# RPi_Pico_2.net
KiCad netlist of a schematic drawn in EasyEDA Pro
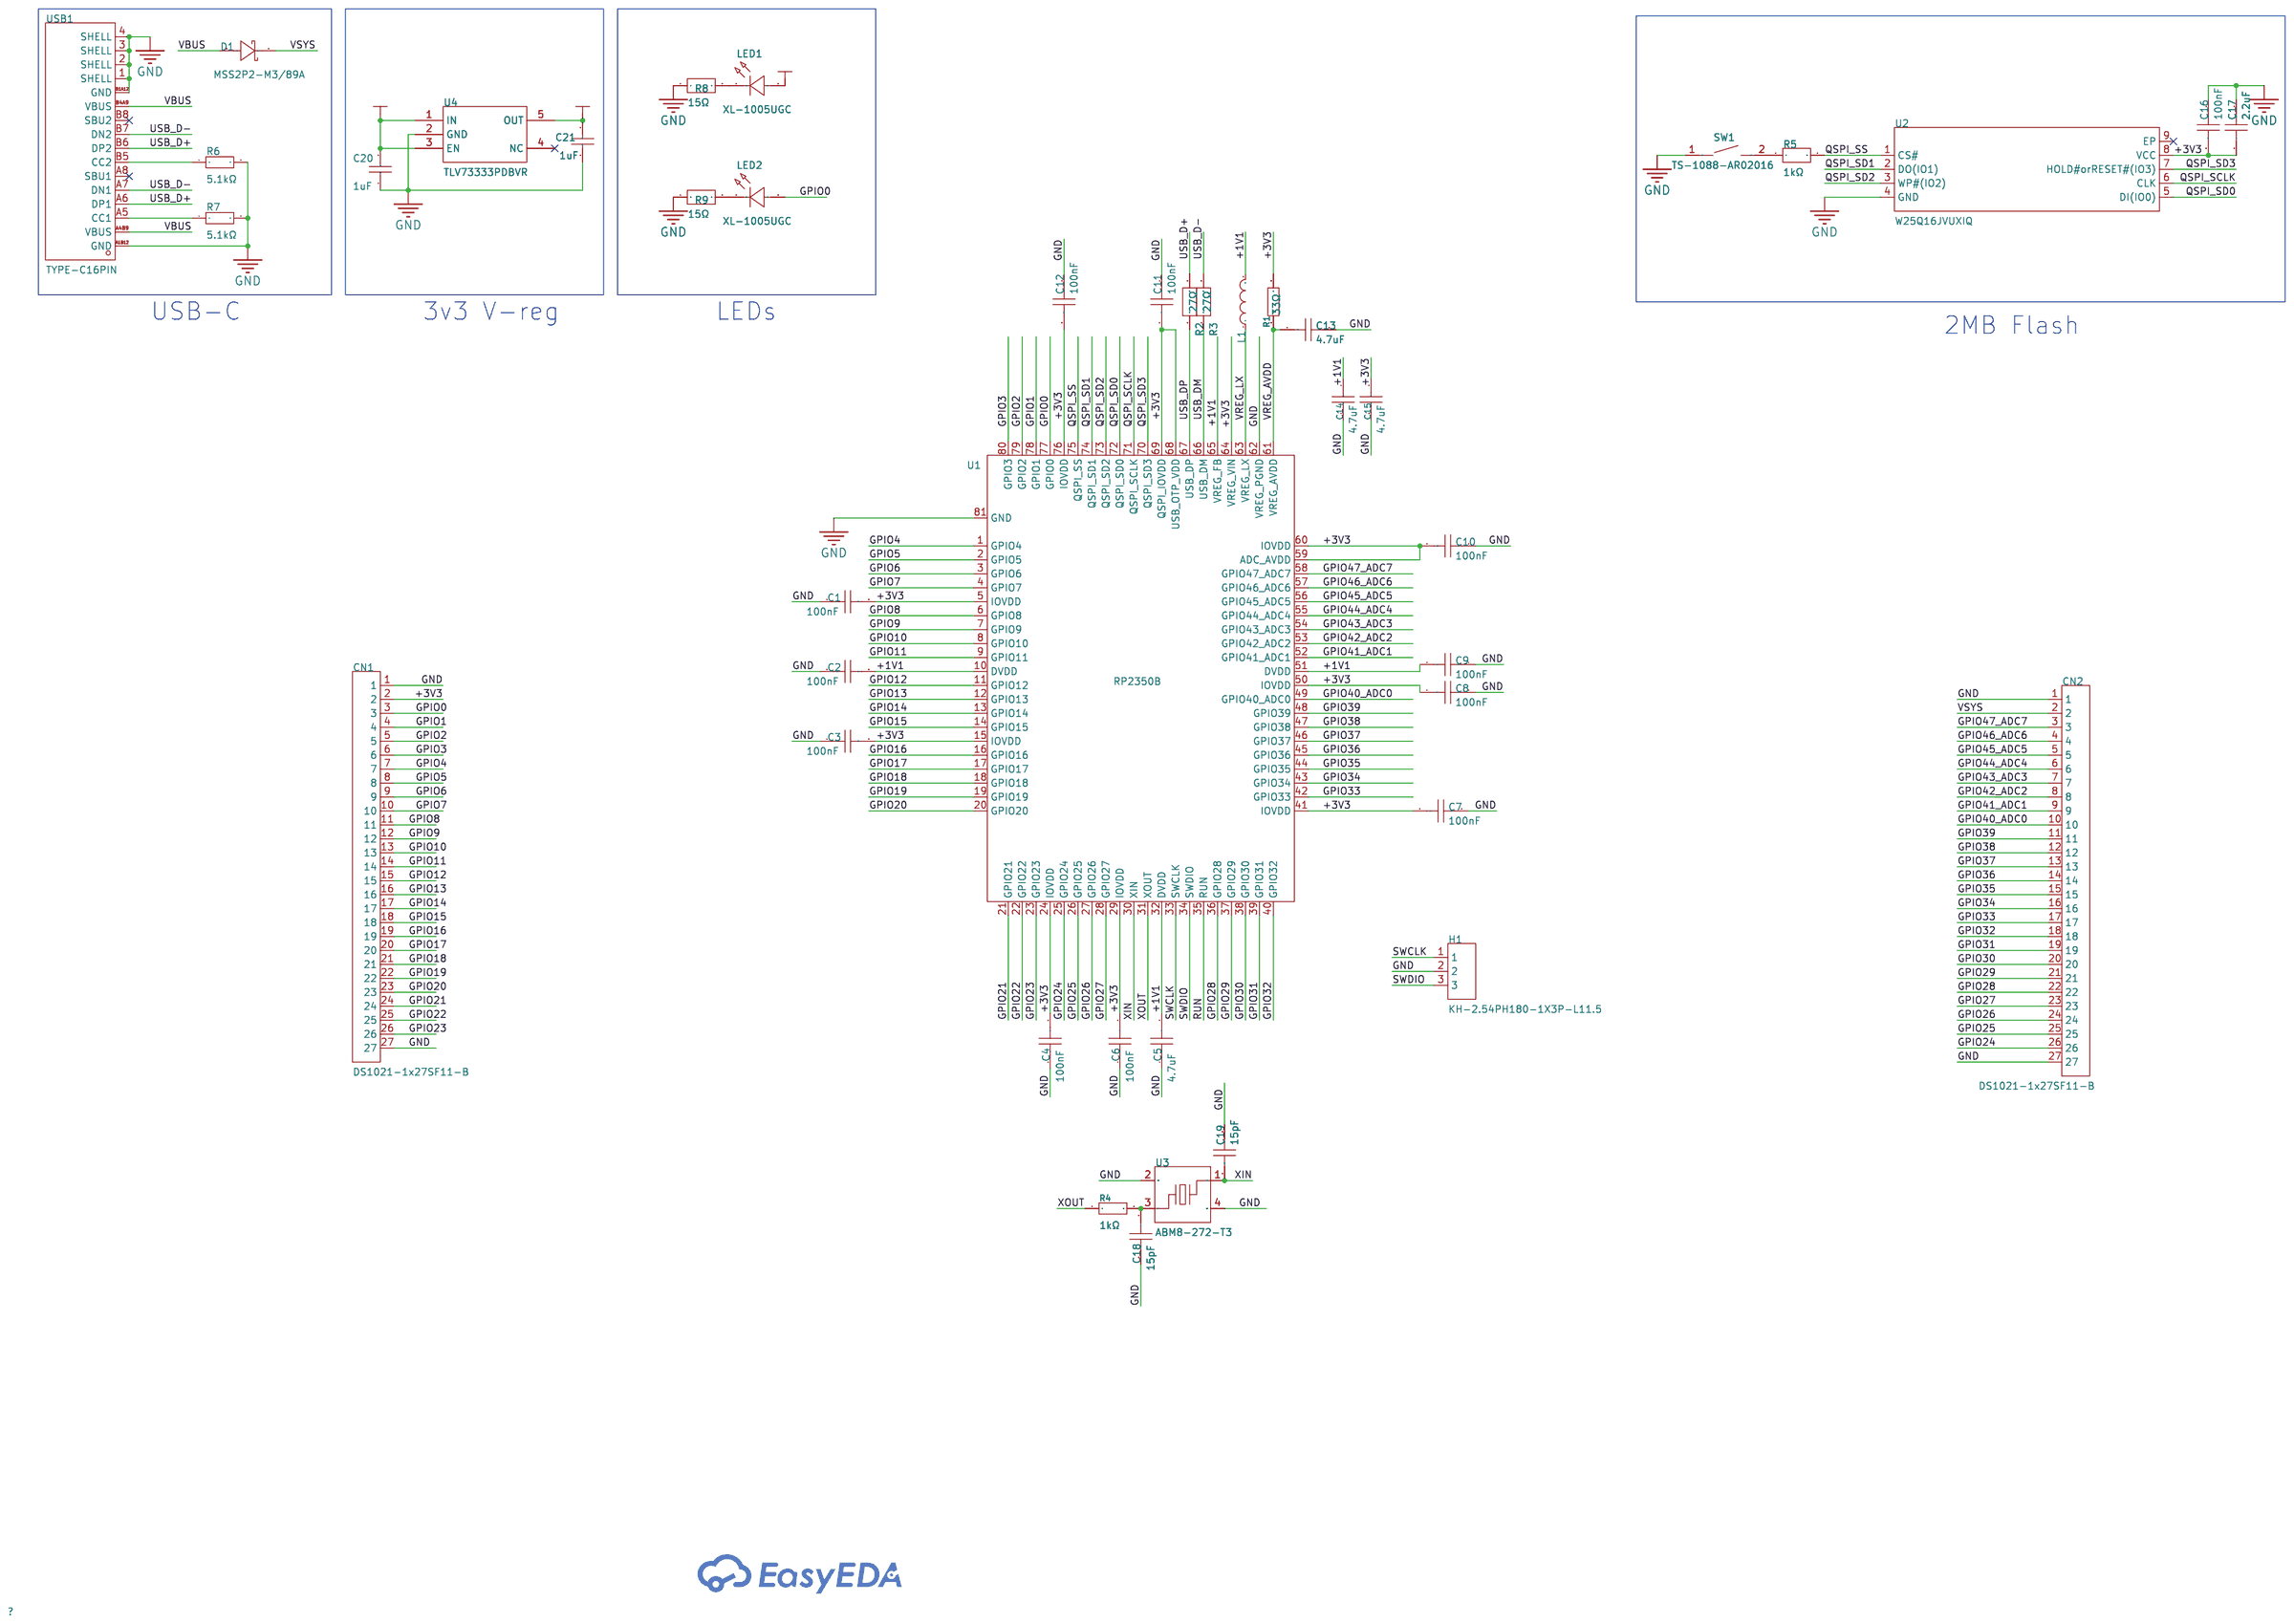
[diagram p0: schematic sheet]

(export (version "E")
  (design (tool "Eeschema 10.0.6"))
  (components
    (comp (ref "C1")
      (value "100nF")
      (footprint "easyedapro:C0201")
      (fields
        (field (name "Manufacturer Part") "GRM033R60J104KE19D")
        (field (name "Manufacturer") "muRata(村田)")
      )
      (libsource (lib "easyedapro") (part "GRM033R60J104KE19D"))
    )
    (comp (ref "C2")
      (value "100nF")
      (footprint "easyedapro:C0201")
      (fields
        (field (name "Manufacturer Part") "GRM033R60J104KE19D")
        (field (name "Manufacturer") "muRata(村田)")
      )
      (libsource (lib "easyedapro") (part "GRM033R60J104KE19D"))
    )
    (comp (ref "C3")
      (value "100nF")
      (footprint "easyedapro:C0201")
      (fields
        (field (name "Manufacturer Part") "GRM033R60J104KE19D")
        (field (name "Manufacturer") "muRata(村田)")
      )
      (libsource (lib "easyedapro") (part "GRM033R60J104KE19D"))
    )
    (comp (ref "C4")
      (value "100nF")
      (footprint "easyedapro:C0201")
      (fields
        (field (name "Manufacturer Part") "GRM033R60J104KE19D")
        (field (name "Manufacturer") "muRata(村田)")
      )
      (libsource (lib "easyedapro") (part "GRM033R60J104KE19D"))
    )
    (comp (ref "C5")
      (value "4.7uF")
      (footprint "easyedapro:C0201")
      (description "Capacitance:4.7uF Tolerance:±20% Tolerance:±20% Voltage Rating:6.3V Temperature Coefficient:X5R")
      (fields
        (field (name "Manufacturer Part") "GRM035R60J475ME15D")
        (field (name "Manufacturer") "muRata(村田)")
      )
      (libsource (lib "easyedapro") (part "GRM035R60J475ME15D"))
    )
    (comp (ref "C6")
      (value "100nF")
      (footprint "easyedapro:C0201")
      (fields
        (field (name "Manufacturer Part") "GRM033R60J104KE19D")
        (field (name "Manufacturer") "muRata(村田)")
      )
      (libsource (lib "easyedapro") (part "GRM033R60J104KE19D"))
    )
    (comp (ref "C7")
      (value "100nF")
      (footprint "easyedapro:C0201")
      (fields
        (field (name "Manufacturer Part") "GRM033R60J104KE19D")
        (field (name "Manufacturer") "muRata(村田)")
      )
      (libsource (lib "easyedapro") (part "GRM033R60J104KE19D"))
    )
    (comp (ref "C8")
      (value "100nF")
      (footprint "easyedapro:C0201")
      (fields
        (field (name "Manufacturer Part") "GRM033R60J104KE19D")
        (field (name "Manufacturer") "muRata(村田)")
      )
      (libsource (lib "easyedapro") (part "GRM033R60J104KE19D"))
    )
    (comp (ref "C9")
      (value "100nF")
      (footprint "easyedapro:C0201")
      (fields
        (field (name "Manufacturer Part") "GRM033R60J104KE19D")
        (field (name "Manufacturer") "muRata(村田)")
      )
      (libsource (lib "easyedapro") (part "GRM033R60J104KE19D"))
    )
    (comp (ref "C10")
      (value "100nF")
      (footprint "easyedapro:C0201")
      (fields
        (field (name "Manufacturer Part") "GRM033R60J104KE19D")
        (field (name "Manufacturer") "muRata(村田)")
      )
      (libsource (lib "easyedapro") (part "GRM033R60J104KE19D"))
    )
    (comp (ref "C11")
      (value "100nF")
      (footprint "easyedapro:C0201")
      (fields
        (field (name "Manufacturer Part") "GRM033R60J104KE19D")
        (field (name "Manufacturer") "muRata(村田)")
      )
      (libsource (lib "easyedapro") (part "GRM033R60J104KE19D"))
    )
    (comp (ref "C12")
      (value "100nF")
      (footprint "easyedapro:C0201")
      (fields
        (field (name "Manufacturer Part") "GRM033R60J104KE19D")
        (field (name "Manufacturer") "muRata(村田)")
      )
      (libsource (lib "easyedapro") (part "GRM033R60J104KE19D"))
    )
    (comp (ref "C13")
      (value "4.7uF")
      (footprint "easyedapro:C0201")
      (description "Capacitance:4.7uF Tolerance:±20% Tolerance:±20% Voltage Rating:6.3V Temperature Coefficient:X5R")
      (fields
        (field (name "Manufacturer Part") "GRM035R60J475ME15D")
        (field (name "Manufacturer") "muRata(村田)")
      )
      (libsource (lib "easyedapro") (part "GRM035R60J475ME15D"))
    )
    (comp (ref "C14")
      (value "4.7uF")
      (footprint "easyedapro:C0402")
      (description "Capacitance:4.7uF Tolerance:±20% Tolerance:±20% Voltage Rating:10V Temperature Coefficient:X5R")
      (fields
        (field (name "Manufacturer Part") "CL05A475MP5NRNC")
        (field (name "Manufacturer") "SAMSUNG(三星)")
      )
      (libsource (lib "easyedapro") (part "CL05A475MP5NRNC"))
    )
    (comp (ref "C15")
      (value "4.7uF")
      (footprint "easyedapro:C0402")
      (description "Capacitance:4.7uF Tolerance:±20% Tolerance:±20% Voltage Rating:10V Temperature Coefficient:X5R")
      (fields
        (field (name "Manufacturer Part") "CL05A475MP5NRNC")
        (field (name "Manufacturer") "SAMSUNG(三星)")
      )
      (libsource (lib "easyedapro") (part "CL05A475MP5NRNC"))
    )
    (comp (ref "C16")
      (value "100nF")
      (footprint "easyedapro:C0201")
      (fields
        (field (name "Manufacturer Part") "GRM033R60J104KE19D")
        (field (name "Manufacturer") "muRata(村田)")
      )
      (libsource (lib "easyedapro") (part "GRM033R60J104KE19D"))
    )
    (comp (ref "C17")
      (value "2.2uF")
      (footprint "easyedapro:C0201")
      (description "Capacitance:2.2uF Tolerance:±20% Tolerance:±20% Voltage Rating:6.3V Temperature Coefficient:X5R")
      (fields (field (name "Manufacturer Part") "0201X225M6R3NT") (field (name "Manufacturer") "FH(风华)"))
      (libsource (lib "easyedapro") (part "0201X225M6R3NT"))
    )
    (comp (ref "C18")
      (value "15pF")
      (footprint "easyedapro:C0201")
      (fields
        (field (name "Manufacturer Part") "CC0201JRNPO9BN150")
        (field (name "Manufacturer") "YAGEO(国巨)")
      )
      (libsource (lib "easyedapro") (part "CC0201JRNPO9BN150"))
    )
    (comp (ref "C19")
      (value "15pF")
      (footprint "easyedapro:C0201")
      (fields
        (field (name "Manufacturer Part") "CC0201JRNPO9BN150")
        (field (name "Manufacturer") "YAGEO(国巨)")
      )
      (libsource (lib "easyedapro") (part "CC0201JRNPO9BN150"))
    )
    (comp (ref "C20")
      (value "1uF")
      (footprint "easyedapro:C0201")
      (description "Capacitance:1uF Tolerance:±20% Tolerance:±20% Voltage Rating:6.3V Temperature Coefficient:X5R")
      (fields
        (field (name "Manufacturer Part") "CL03A105MQ3CSNH")
        (field (name "Manufacturer") "SAMSUNG(三星)")
      )
      (libsource (lib "easyedapro") (part "CL03A105MQ3CSNH"))
    )
    (comp (ref "C21")
      (value "1uF")
      (footprint "easyedapro:C0201")
      (description "Capacitance:1uF Tolerance:±20% Tolerance:±20% Voltage Rating:6.3V Temperature Coefficient:X5R")
      (fields
        (field (name "Manufacturer Part") "CL03A105MQ3CSNH")
        (field (name "Manufacturer") "SAMSUNG(三星)")
      )
      (libsource (lib "easyedapro") (part "CL03A105MQ3CSNH"))
    )
    (comp (ref "CN1")
      (value "DS1021-1x27SF11-B")
      (footprint "easyedapro:HDR-TH_27P-P2.54-V-M")
      (fields (field (name "Manufacturer") "CONNFLY"))
      (libsource (lib "easyedapro") (part "DS1021-1X27SF11-B"))
    )
    (comp (ref "CN2")
      (value "DS1021-1x27SF11-B")
      (footprint "easyedapro:HDR-TH_27P-P2.54-V-M")
      (fields (field (name "Manufacturer") "CONNFLY"))
      (libsource (lib "easyedapro") (part "DS1021-1X27SF11-B"))
    )
    (comp (ref "D1")
      (value "MSS2P2-M3/89A")
      (footprint "easyedapro:DO-219AD_L2.2-W1.3-L-RD_MSS2P2-M3-89A")
      (fields (field (name "Manufacturer") "VISHAY(威世)"))
      (libsource (lib "easyedapro") (part "MSS2P2-M3/89A"))
    )
    (comp (ref "H1")
      (value "KH-2.54PH180-1X3P-L11.5")
      (footprint "easyedapro:HDR-TH_3P-P2.54-V-M")
      (fields (field (name "Manufacturer") "kinghelm(金航标)"))
      (libsource (lib "easyedapro") (part "KH-2.54PH180-1X3P-L11.5"))
    )
    (comp (ref "L1")
      (value "AOTA-B201610S3R3-101-T")
      (footprint "easyedapro:IND-SMD_L2.0-W1.6_AOTA-B201610S3R3-101-T")
      (fields (field (name "Manufacturer") "ABRACON"))
      (libsource (lib "easyedapro") (part "AOTA-B201610S3R3-101-T"))
    )
    (comp (ref "LED1")
      (value "XL-1005UGC")
      (footprint "easyedapro:LED0402-RD_GREEN")
      (fields (field (name "Manufacturer") "XINGLIGHT(成兴光)"))
      (libsource (lib "easyedapro") (part "XL-1005UGC"))
    )
    (comp (ref "LED2")
      (value "XL-1005UGC")
      (footprint "easyedapro:LED0402-RD_GREEN")
      (fields (field (name "Manufacturer") "XINGLIGHT(成兴光)"))
      (libsource (lib "easyedapro") (part "XL-1005UGC"))
    )
    (comp (ref "R1")
      (value "33Ω")
      (footprint "easyedapro:R0201")
      (fields
        (field (name "Manufacturer Part") "0201WMJ0330TEE")
        (field (name "Manufacturer") "UNI-ROYAL(厚声)")
      )
      (libsource (lib "easyedapro") (part "0201WMJ0330TEE"))
    )
    (comp (ref "R2")
      (value "27Ω")
      (footprint "easyedapro:R0201")
      (fields
        (field (name "Manufacturer Part") "0201WMF270JTEE")
        (field (name "Manufacturer") "UNI-ROYAL(厚声)")
      )
      (libsource (lib "easyedapro") (part "0201WMF270JTEE"))
    )
    (comp (ref "R3")
      (value "27Ω")
      (footprint "easyedapro:R0201")
      (fields
        (field (name "Manufacturer Part") "0201WMF270JTEE")
        (field (name "Manufacturer") "UNI-ROYAL(厚声)")
      )
      (libsource (lib "easyedapro") (part "0201WMF270JTEE"))
    )
    (comp (ref "R4")
      (value "1kΩ")
      (footprint "easyedapro:R0201")
      (fields (field (name "Manufacturer Part") "RTT01102JTH") (field (name "Manufacturer") "RALEC(旺诠)"))
      (libsource (lib "easyedapro") (part "RTT01102JTH"))
    )
    (comp (ref "R5")
      (value "1kΩ")
      (footprint "easyedapro:R0201")
      (fields (field (name "Manufacturer Part") "FRC0201F1001TS") (field (name "Manufacturer") "FOJAN(富捷)"))
      (libsource (lib "easyedapro") (part "FRC0201F1001TS"))
    )
    (comp (ref "R6")
      (value "5.1kΩ")
      (footprint "easyedapro:R0201")
      (fields (field (name "Manufacturer Part") "RC0201FR-075K1L") (field (name "Manufacturer") "YAGEO(国巨)"))
      (libsource (lib "easyedapro") (part "RC0201FR-075K1L"))
    )
    (comp (ref "R7")
      (value "5.1kΩ")
      (footprint "easyedapro:R0201")
      (fields (field (name "Manufacturer Part") "RC0201FR-075K1L") (field (name "Manufacturer") "YAGEO(国巨)"))
      (libsource (lib "easyedapro") (part "RC0201FR-075K1L"))
    )
    (comp (ref "R8")
      (value "15Ω")
      (footprint "easyedapro:R0402")
      (fields (field (name "Manufacturer Part") "SCR0402J15R") (field (name "Manufacturer") "VO(翔胜)"))
      (libsource (lib "easyedapro") (part "SCR0402J15R"))
    )
    (comp (ref "R9")
      (value "15Ω")
      (footprint "easyedapro:R0402")
      (fields (field (name "Manufacturer Part") "SCR0402J15R") (field (name "Manufacturer") "VO(翔胜)"))
      (libsource (lib "easyedapro") (part "SCR0402J15R"))
    )
    (comp (ref "SW1")
      (value "TS-1088-AR02016")
      (footprint "easyedapro:SW-SMD_L3.9-W3.0-P4.45")
      (fields (field (name "Manufacturer") "XUNPU(讯普)"))
      (libsource (lib "easyedapro") (part "TS-1088-AR02016"))
    )
    (comp (ref "U1")
      (value "RP2350B")
      (footprint "easyedapro:QFN-80_L10.0-W10.0-P0.40-TL-EP3.4")
      (fields (field (name "Manufacturer") "Raspberry Pi(树莓派)"))
      (libsource (lib "easyedapro") (part "RP2350B_C42415655"))
    )
    (comp (ref "U2")
      (value "W25Q16JVUXIQ")
      (footprint "easyedapro:USON-8_L3.0-W2.0-P0.50-BL-EP")
      (fields (field (name "Manufacturer") "Winbond(华邦)"))
      (libsource (lib "easyedapro") (part "W25Q16JVUXIQ"))
    )
    (comp (ref "U3")
      (value "ABM8-272-T3")
      (footprint "easyedapro:CRYSTAL-SMD_4P-L3.2-W2.5-BL")
      (fields (field (name "Manufacturer") "ABRACON"))
      (libsource (lib "easyedapro") (part "ABM8-272-T3_C20625731"))
    )
    (comp (ref "U4")
      (value "TLV73333PDBVR")
      (footprint "easyedapro:SOT-23-5_L3.0-W1.7-P0.95-LS2.8-BR")
      (fields (field (name "Manufacturer") "TI(德州仪器)"))
      (libsource (lib "easyedapro") (part "TLV73333PDBVR"))
    )
    (comp (ref "USB1")
      (value "TYPE-C16PIN")
      (footprint "easyedapro:USB-C-SMD_TYPE-C16PIN")
      (fields (field (name "Manufacturer") "SHOU HAN(首韩)"))
      (libsource (lib "easyedapro") (part "TYPE-C16PIN"))
    )
  )
  (nets
    (net (code "1") (name "+3V3") (class "Default")
      (node (ref "C1") (pin "2") (pinfunction "2_2") (pintype "unspecified"))
      (node (ref "C10") (pin "2") (pinfunction "2_2") (pintype "unspecified"))
      (node (ref "C11") (pin "2") (pinfunction "2_2") (pintype "unspecified"))
      (node (ref "C12") (pin "2") (pinfunction "2_2") (pintype "unspecified"))
      (node (ref "C15") (pin "2") (pinfunction "2_2") (pintype "input"))
      (node (ref "C16") (pin "2") (pinfunction "2_2") (pintype "unspecified"))
      (node (ref "C17") (pin "1") (pinfunction "1_1") (pintype "unspecified"))
      (node (ref "C21") (pin "2") (pinfunction "2_2") (pintype "input"))
      (node (ref "C3") (pin "2") (pinfunction "2_2") (pintype "unspecified"))
      (node (ref "C4") (pin "2") (pinfunction "2_2") (pintype "unspecified"))
      (node (ref "C6") (pin "2") (pinfunction "2_2") (pintype "unspecified"))
      (node (ref "C7") (pin "2") (pinfunction "2_2") (pintype "unspecified"))
      (node (ref "C8") (pin "2") (pinfunction "2_2") (pintype "unspecified"))
      (node (ref "CN1") (pin "2") (pinfunction "2_2") (pintype "unspecified"))
      (node (ref "LED1") (pin "2") (pinfunction "A_2") (pintype "unspecified"))
      (node (ref "R1") (pin "2") (pinfunction "2_2") (pintype "input"))
      (node (ref "U1") (pin "15") (pinfunction "IOVDD_15") (pintype "unspecified"))
      (node (ref "U1") (pin "24") (pinfunction "IOVDD_24") (pintype "unspecified"))
      (node (ref "U1") (pin "29") (pinfunction "IOVDD_29") (pintype "unspecified"))
      (node (ref "U1") (pin "41") (pinfunction "IOVDD_41") (pintype "unspecified"))
      (node (ref "U1") (pin "5") (pinfunction "IOVDD_5") (pintype "unspecified"))
      (node (ref "U1") (pin "50") (pinfunction "IOVDD_50") (pintype "unspecified"))
      (node (ref "U1") (pin "59") (pinfunction "ADC_AVDD_59") (pintype "unspecified"))
      (node (ref "U1") (pin "60") (pinfunction "IOVDD_60") (pintype "unspecified"))
      (node (ref "U1") (pin "64") (pinfunction "VREG_VIN_64") (pintype "unspecified"))
      (node (ref "U1") (pin "68") (pinfunction "USB_OTP_VDD_68") (pintype "unspecified"))
      (node (ref "U1") (pin "69") (pinfunction "QSPI_IOVDD_69") (pintype "unspecified"))
      (node (ref "U1") (pin "76") (pinfunction "IOVDD_76") (pintype "unspecified"))
      (node (ref "U2") (pin "8") (pinfunction "VCC_8") (pintype "unspecified"))
      (node (ref "U4") (pin "5") (pinfunction "OUT_5") (pintype "unspecified"))
    )
    (net (code "2") (name "/+1V1") (class "Default")
      (node (ref "C14") (pin "2") (pinfunction "2_2") (pintype "input"))
      (node (ref "C2") (pin "2") (pinfunction "2_2") (pintype "unspecified"))
      (node (ref "C5") (pin "2") (pinfunction "2_2") (pintype "unspecified"))
      (node (ref "C9") (pin "2") (pinfunction "2_2") (pintype "unspecified"))
      (node (ref "L1") (pin "2") (pinfunction "2_2") (pintype "unspecified"))
      (node (ref "U1") (pin "10") (pinfunction "DVDD_10") (pintype "unspecified"))
      (node (ref "U1") (pin "32") (pinfunction "DVDD_32") (pintype "unspecified"))
      (node (ref "U1") (pin "51") (pinfunction "DVDD_51") (pintype "unspecified"))
      (node (ref "U1") (pin "65") (pinfunction "VREG_FB_65") (pintype "unspecified"))
    )
    (net (code "3") (name "/GPIO0") (class "Default")
      (node (ref "CN1") (pin "3") (pinfunction "3_3") (pintype "unspecified"))
      (node (ref "LED2") (pin "2") (pinfunction "A_2") (pintype "unspecified"))
      (node (ref "U1") (pin "77") (pinfunction "GPIO0_77") (pintype "unspecified"))
    )
    (net (code "4") (name "/GPIO1") (class "Default")
      (node (ref "CN1") (pin "4") (pinfunction "4_4") (pintype "unspecified"))
      (node (ref "U1") (pin "78") (pinfunction "GPIO1_78") (pintype "unspecified"))
    )
    (net (code "5") (name "/GPIO2") (class "Default")
      (node (ref "CN1") (pin "5") (pinfunction "5_5") (pintype "unspecified"))
      (node (ref "U1") (pin "79") (pinfunction "GPIO2_79") (pintype "unspecified"))
    )
    (net (code "6") (name "/GPIO3") (class "Default")
      (node (ref "CN1") (pin "6") (pinfunction "6_6") (pintype "unspecified"))
      (node (ref "U1") (pin "80") (pinfunction "GPIO3_80") (pintype "unspecified"))
    )
    (net (code "7") (name "/GPIO4") (class "Default")
      (node (ref "CN1") (pin "7") (pinfunction "7_7") (pintype "unspecified"))
      (node (ref "U1") (pin "1") (pinfunction "GPIO4_1") (pintype "unspecified"))
    )
    (net (code "8") (name "/GPIO5") (class "Default")
      (node (ref "CN1") (pin "8") (pinfunction "8_8") (pintype "unspecified"))
      (node (ref "U1") (pin "2") (pinfunction "GPIO5_2") (pintype "unspecified"))
    )
    (net (code "9") (name "/GPIO6") (class "Default")
      (node (ref "CN1") (pin "9") (pinfunction "9_9") (pintype "unspecified"))
      (node (ref "U1") (pin "3") (pinfunction "GPIO6_3") (pintype "unspecified"))
    )
    (net (code "10") (name "/GPIO7") (class "Default")
      (node (ref "CN1") (pin "10") (pinfunction "10_10") (pintype "unspecified"))
      (node (ref "U1") (pin "4") (pinfunction "GPIO7_4") (pintype "unspecified"))
    )
    (net (code "11") (name "/GPIO8") (class "Default")
      (node (ref "CN1") (pin "11") (pinfunction "11_11") (pintype "unspecified"))
      (node (ref "U1") (pin "6") (pinfunction "GPIO8_6") (pintype "unspecified"))
    )
    (net (code "12") (name "/GPIO9") (class "Default")
      (node (ref "CN1") (pin "12") (pinfunction "12_12") (pintype "unspecified"))
      (node (ref "U1") (pin "7") (pinfunction "GPIO9_7") (pintype "unspecified"))
    )
    (net (code "13") (name "/GPIO10") (class "Default")
      (node (ref "CN1") (pin "13") (pinfunction "13_13") (pintype "unspecified"))
      (node (ref "U1") (pin "8") (pinfunction "GPIO10_8") (pintype "unspecified"))
    )
    (net (code "14") (name "/GPIO11") (class "Default")
      (node (ref "CN1") (pin "14") (pinfunction "14_14") (pintype "unspecified"))
      (node (ref "U1") (pin "9") (pinfunction "GPIO11_9") (pintype "unspecified"))
    )
    (net (code "15") (name "/GPIO12") (class "Default")
      (node (ref "CN1") (pin "15") (pinfunction "15_15") (pintype "unspecified"))
      (node (ref "U1") (pin "11") (pinfunction "GPIO12_11") (pintype "unspecified"))
    )
    (net (code "16") (name "/GPIO13") (class "Default")
      (node (ref "CN1") (pin "16") (pinfunction "16_16") (pintype "unspecified"))
      (node (ref "U1") (pin "12") (pinfunction "GPIO13_12") (pintype "unspecified"))
    )
    (net (code "17") (name "/GPIO14") (class "Default")
      (node (ref "CN1") (pin "17") (pinfunction "17_17") (pintype "unspecified"))
      (node (ref "U1") (pin "13") (pinfunction "GPIO14_13") (pintype "unspecified"))
    )
    (net (code "18") (name "/GPIO15") (class "Default")
      (node (ref "CN1") (pin "18") (pinfunction "18_18") (pintype "unspecified"))
      (node (ref "U1") (pin "14") (pinfunction "GPIO15_14") (pintype "unspecified"))
    )
    (net (code "19") (name "/GPIO16") (class "Default")
      (node (ref "CN1") (pin "19") (pinfunction "19_19") (pintype "unspecified"))
      (node (ref "U1") (pin "16") (pinfunction "GPIO16_16") (pintype "unspecified"))
    )
    (net (code "20") (name "/GPIO17") (class "Default")
      (node (ref "CN1") (pin "20") (pinfunction "20_20") (pintype "unspecified"))
      (node (ref "U1") (pin "17") (pinfunction "GPIO17_17") (pintype "unspecified"))
    )
    (net (code "21") (name "/GPIO18") (class "Default")
      (node (ref "CN1") (pin "21") (pinfunction "21_21") (pintype "unspecified"))
      (node (ref "U1") (pin "18") (pinfunction "GPIO18_18") (pintype "unspecified"))
    )
    (net (code "22") (name "/GPIO19") (class "Default")
      (node (ref "CN1") (pin "22") (pinfunction "22_22") (pintype "unspecified"))
      (node (ref "U1") (pin "19") (pinfunction "GPIO19_19") (pintype "unspecified"))
    )
    (net (code "23") (name "/GPIO20") (class "Default")
      (node (ref "CN1") (pin "23") (pinfunction "23_23") (pintype "unspecified"))
      (node (ref "U1") (pin "20") (pinfunction "GPIO20_20") (pintype "unspecified"))
    )
    (net (code "24") (name "/GPIO21") (class "Default")
      (node (ref "CN1") (pin "24") (pinfunction "24_24") (pintype "unspecified"))
      (node (ref "U1") (pin "21") (pinfunction "GPIO21_21") (pintype "unspecified"))
    )
    (net (code "25") (name "/GPIO22") (class "Default")
      (node (ref "CN1") (pin "25") (pinfunction "25_25") (pintype "unspecified"))
      (node (ref "U1") (pin "22") (pinfunction "GPIO22_22") (pintype "unspecified"))
    )
    (net (code "26") (name "/GPIO23") (class "Default")
      (node (ref "CN1") (pin "26") (pinfunction "26_26") (pintype "unspecified"))
      (node (ref "U1") (pin "23") (pinfunction "GPIO23_23") (pintype "unspecified"))
    )
    (net (code "27") (name "/GPIO24") (class "Default")
      (node (ref "CN2") (pin "26") (pinfunction "26_26") (pintype "unspecified"))
      (node (ref "U1") (pin "25") (pinfunction "GPIO24_25") (pintype "unspecified"))
    )
    (net (code "28") (name "/GPIO25") (class "Default")
      (node (ref "CN2") (pin "25") (pinfunction "25_25") (pintype "unspecified"))
      (node (ref "U1") (pin "26") (pinfunction "GPIO25_26") (pintype "unspecified"))
    )
    (net (code "29") (name "/GPIO26") (class "Default")
      (node (ref "CN2") (pin "24") (pinfunction "24_24") (pintype "unspecified"))
      (node (ref "U1") (pin "27") (pinfunction "GPIO26_27") (pintype "unspecified"))
    )
    (net (code "30") (name "/GPIO27") (class "Default")
      (node (ref "CN2") (pin "23") (pinfunction "23_23") (pintype "unspecified"))
      (node (ref "U1") (pin "28") (pinfunction "GPIO27_28") (pintype "unspecified"))
    )
    (net (code "31") (name "/GPIO28") (class "Default")
      (node (ref "CN2") (pin "22") (pinfunction "22_22") (pintype "unspecified"))
      (node (ref "U1") (pin "36") (pinfunction "GPIO28_36") (pintype "unspecified"))
    )
    (net (code "32") (name "/GPIO29") (class "Default")
      (node (ref "CN2") (pin "21") (pinfunction "21_21") (pintype "unspecified"))
      (node (ref "U1") (pin "37") (pinfunction "GPIO29_37") (pintype "unspecified"))
    )
    (net (code "33") (name "/GPIO30") (class "Default")
      (node (ref "CN2") (pin "20") (pinfunction "20_20") (pintype "unspecified"))
      (node (ref "U1") (pin "38") (pinfunction "GPIO30_38") (pintype "unspecified"))
    )
    (net (code "34") (name "/GPIO31") (class "Default")
      (node (ref "CN2") (pin "19") (pinfunction "19_19") (pintype "unspecified"))
      (node (ref "U1") (pin "39") (pinfunction "GPIO31_39") (pintype "unspecified"))
    )
    (net (code "35") (name "/GPIO32") (class "Default")
      (node (ref "CN2") (pin "18") (pinfunction "18_18") (pintype "unspecified"))
      (node (ref "U1") (pin "40") (pinfunction "GPIO32_40") (pintype "unspecified"))
    )
    (net (code "36") (name "/GPIO33") (class "Default")
      (node (ref "CN2") (pin "17") (pinfunction "17_17") (pintype "unspecified"))
      (node (ref "U1") (pin "42") (pinfunction "GPIO33_42") (pintype "unspecified"))
    )
    (net (code "37") (name "/GPIO34") (class "Default")
      (node (ref "CN2") (pin "16") (pinfunction "16_16") (pintype "unspecified"))
      (node (ref "U1") (pin "43") (pinfunction "GPIO34_43") (pintype "unspecified"))
    )
    (net (code "38") (name "/GPIO35") (class "Default")
      (node (ref "CN2") (pin "15") (pinfunction "15_15") (pintype "unspecified"))
      (node (ref "U1") (pin "44") (pinfunction "GPIO35_44") (pintype "unspecified"))
    )
    (net (code "39") (name "/GPIO36") (class "Default")
      (node (ref "CN2") (pin "14") (pinfunction "14_14") (pintype "unspecified"))
      (node (ref "U1") (pin "45") (pinfunction "GPIO36_45") (pintype "unspecified"))
    )
    (net (code "40") (name "/GPIO37") (class "Default")
      (node (ref "CN2") (pin "13") (pinfunction "13_13") (pintype "unspecified"))
      (node (ref "U1") (pin "46") (pinfunction "GPIO37_46") (pintype "unspecified"))
    )
    (net (code "41") (name "/GPIO38") (class "Default")
      (node (ref "CN2") (pin "12") (pinfunction "12_12") (pintype "unspecified"))
      (node (ref "U1") (pin "47") (pinfunction "GPIO38_47") (pintype "unspecified"))
    )
    (net (code "42") (name "/GPIO39") (class "Default")
      (node (ref "CN2") (pin "11") (pinfunction "11_11") (pintype "unspecified"))
      (node (ref "U1") (pin "48") (pinfunction "GPIO39_48") (pintype "unspecified"))
    )
    (net (code "43") (name "/GPIO40_ADC0") (class "Default")
      (node (ref "CN2") (pin "10") (pinfunction "10_10") (pintype "unspecified"))
      (node (ref "U1") (pin "49") (pinfunction "GPIO40_ADC0_49") (pintype "unspecified"))
    )
    (net (code "44") (name "/GPIO41_ADC1") (class "Default")
      (node (ref "CN2") (pin "9") (pinfunction "9_9") (pintype "unspecified"))
      (node (ref "U1") (pin "52") (pinfunction "GPIO41_ADC1_52") (pintype "unspecified"))
    )
    (net (code "45") (name "/GPIO42_ADC2") (class "Default")
      (node (ref "CN2") (pin "8") (pinfunction "8_8") (pintype "unspecified"))
      (node (ref "U1") (pin "53") (pinfunction "GPIO42_ADC2_53") (pintype "unspecified"))
    )
    (net (code "46") (name "/GPIO43_ADC3") (class "Default")
      (node (ref "CN2") (pin "7") (pinfunction "7_7") (pintype "unspecified"))
      (node (ref "U1") (pin "54") (pinfunction "GPIO43_ADC3_54") (pintype "unspecified"))
    )
    (net (code "47") (name "/GPIO44_ADC4") (class "Default")
      (node (ref "CN2") (pin "6") (pinfunction "6_6") (pintype "unspecified"))
      (node (ref "U1") (pin "55") (pinfunction "GPIO44_ADC4_55") (pintype "unspecified"))
    )
    (net (code "48") (name "/GPIO45_ADC5") (class "Default")
      (node (ref "CN2") (pin "5") (pinfunction "5_5") (pintype "unspecified"))
      (node (ref "U1") (pin "56") (pinfunction "GPIO45_ADC5_56") (pintype "unspecified"))
    )
    (net (code "49") (name "/GPIO46_ADC6") (class "Default")
      (node (ref "CN2") (pin "4") (pinfunction "4_4") (pintype "unspecified"))
      (node (ref "U1") (pin "57") (pinfunction "GPIO46_ADC6_57") (pintype "unspecified"))
    )
    (net (code "50") (name "/GPIO47_ADC7") (class "Default")
      (node (ref "CN2") (pin "3") (pinfunction "3_3") (pintype "unspecified"))
      (node (ref "U1") (pin "58") (pinfunction "GPIO47_ADC7_58") (pintype "unspecified"))
    )
    (net (code "51") (name "/QSPI_SCLK") (class "Default")
      (node (ref "U1") (pin "71") (pinfunction "QSPI_SCLK_71") (pintype "unspecified"))
      (node (ref "U2") (pin "6") (pinfunction "CLK_6") (pintype "unspecified"))
    )
    (net (code "52") (name "/QSPI_SD0") (class "Default")
      (node (ref "U1") (pin "72") (pinfunction "QSPI_SD0_72") (pintype "unspecified"))
      (node (ref "U2") (pin "5") (pinfunction "DI(IO0)_5") (pintype "unspecified"))
    )
    (net (code "53") (name "/QSPI_SD1") (class "Default")
      (node (ref "U1") (pin "74") (pinfunction "QSPI_SD1_74") (pintype "unspecified"))
      (node (ref "U2") (pin "2") (pinfunction "DO(IO1)_2") (pintype "unspecified"))
    )
    (net (code "54") (name "/QSPI_SD2") (class "Default")
      (node (ref "U1") (pin "73") (pinfunction "QSPI_SD2_73") (pintype "unspecified"))
      (node (ref "U2") (pin "3") (pinfunction "WP#(IO2)_3") (pintype "unspecified"))
    )
    (net (code "55") (name "/QSPI_SD3") (class "Default")
      (node (ref "U1") (pin "70") (pinfunction "QSPI_SD3_70") (pintype "unspecified"))
      (node (ref "U2") (pin "7") (pinfunction "HOLD#orRESET#(IO3)_7") (pintype "unspecified"))
    )
    (net (code "56") (name "/QSPI_SS") (class "Default")
      (node (ref "R5") (pin "2") (pinfunction "2_2") (pintype "unspecified"))
      (node (ref "U1") (pin "75") (pinfunction "QSPI_SS_75") (pintype "unspecified"))
      (node (ref "U2") (pin "1") (pinfunction "CS#_1") (pintype "unspecified"))
    )
    (net (code "57") (name "/RUN") (class "Default")
      (node (ref "U1") (pin "35") (pinfunction "RUN_35") (pintype "unspecified"))
    )
    (net (code "58") (name "/SWCLK") (class "Default")
      (node (ref "H1") (pin "1") (pinfunction "1_1") (pintype "unspecified"))
      (node (ref "U1") (pin "33") (pinfunction "SWCLK_33") (pintype "unspecified"))
    )
    (net (code "59") (name "/SWDIO") (class "Default")
      (node (ref "H1") (pin "3") (pinfunction "3_3") (pintype "unspecified"))
      (node (ref "U1") (pin "34") (pinfunction "SWDIO_34") (pintype "unspecified"))
    )
    (net (code "60") (name "/USB_D+") (class "Default")
      (node (ref "R2") (pin "2") (pinfunction "2_2") (pintype "unspecified"))
      (node (ref "USB1") (pin "A6") (pinfunction "DP1_A6") (pintype "unspecified"))
      (node (ref "USB1") (pin "B6") (pinfunction "DP2_B6") (pintype "unspecified"))
    )
    (net (code "61") (name "/USB_D-") (class "Default")
      (node (ref "R3") (pin "2") (pinfunction "2_2") (pintype "unspecified"))
      (node (ref "USB1") (pin "A7") (pinfunction "DN1_A7") (pintype "unspecified"))
      (node (ref "USB1") (pin "B7") (pinfunction "DN2_B7") (pintype "unspecified"))
    )
    (net (code "62") (name "/USB_DM") (class "Default")
      (node (ref "R3") (pin "1") (pinfunction "1_1") (pintype "unspecified"))
      (node (ref "U1") (pin "66") (pinfunction "USB_DM_66") (pintype "unspecified"))
    )
    (net (code "63") (name "/USB_DP") (class "Default")
      (node (ref "R2") (pin "1") (pinfunction "1_1") (pintype "unspecified"))
      (node (ref "U1") (pin "67") (pinfunction "USB_DP_67") (pintype "unspecified"))
    )
    (net (code "64") (name "/VBUS") (class "Default")
      (node (ref "D1") (pin "2") (pinfunction "A_2") (pintype "unspecified"))
      (node (ref "USB1") (pin "A4B9") (pinfunction "VBUS_A4B9") (pintype "unspecified"))
      (node (ref "USB1") (pin "B4A9") (pinfunction "VBUS_B4A9") (pintype "unspecified"))
    )
    (net (code "65") (name "/VREG_AVDD") (class "Default")
      (node (ref "C13") (pin "2") (pinfunction "2_2") (pintype "unspecified"))
      (node (ref "R1") (pin "1") (pinfunction "1_1") (pintype "input"))
      (node (ref "U1") (pin "61") (pinfunction "VREG_AVDD_61") (pintype "unspecified"))
    )
    (net (code "66") (name "/VREG_LX") (class "Default")
      (node (ref "L1") (pin "1") (pinfunction "1_1") (pintype "unspecified"))
      (node (ref "U1") (pin "63") (pinfunction "VREG_LX_63") (pintype "unspecified"))
    )
    (net (code "67") (name "/XIN") (class "Default")
      (node (ref "C19") (pin "1") (pinfunction "1_1") (pintype "unspecified"))
      (node (ref "U1") (pin "30") (pinfunction "XIN_30") (pintype "unspecified"))
      (node (ref "U3") (pin "1") (pinfunction "1_1") (pintype "input"))
    )
    (net (code "68") (name "/XOUT") (class "Default")
      (node (ref "R4") (pin "1") (pinfunction "1_1") (pintype "input"))
      (node (ref "U1") (pin "31") (pinfunction "XOUT_31") (pintype "unspecified"))
    )
    (net (code "69") (name "GND") (class "Default")
      (node (ref "C1") (pin "1") (pinfunction "1_1") (pintype "unspecified"))
      (node (ref "C10") (pin "1") (pinfunction "1_1") (pintype "unspecified"))
      (node (ref "C11") (pin "1") (pinfunction "1_1") (pintype "unspecified"))
      (node (ref "C12") (pin "1") (pinfunction "1_1") (pintype "unspecified"))
      (node (ref "C13") (pin "1") (pinfunction "1_1") (pintype "unspecified"))
      (node (ref "C14") (pin "1") (pinfunction "1_1") (pintype "input"))
      (node (ref "C15") (pin "1") (pinfunction "1_1") (pintype "input"))
      (node (ref "C16") (pin "1") (pinfunction "1_1") (pintype "unspecified"))
      (node (ref "C17") (pin "2") (pinfunction "2_2") (pintype "unspecified"))
      (node (ref "C18") (pin "1") (pinfunction "1_1") (pintype "unspecified"))
      (node (ref "C19") (pin "2") (pinfunction "2_2") (pintype "unspecified"))
      (node (ref "C2") (pin "1") (pinfunction "1_1") (pintype "unspecified"))
      (node (ref "C20") (pin "1") (pinfunction "1_1") (pintype "input"))
      (node (ref "C21") (pin "1") (pinfunction "1_1") (pintype "input"))
      (node (ref "C3") (pin "1") (pinfunction "1_1") (pintype "unspecified"))
      (node (ref "C4") (pin "1") (pinfunction "1_1") (pintype "unspecified"))
      (node (ref "C5") (pin "1") (pinfunction "1_1") (pintype "unspecified"))
      (node (ref "C6") (pin "1") (pinfunction "1_1") (pintype "unspecified"))
      (node (ref "C7") (pin "1") (pinfunction "1_1") (pintype "unspecified"))
      (node (ref "C8") (pin "1") (pinfunction "1_1") (pintype "unspecified"))
      (node (ref "C9") (pin "1") (pinfunction "1_1") (pintype "unspecified"))
      (node (ref "CN1") (pin "1") (pinfunction "1_1") (pintype "unspecified"))
      (node (ref "CN1") (pin "27") (pinfunction "27_27") (pintype "unspecified"))
      (node (ref "CN2") (pin "1") (pinfunction "1_1") (pintype "unspecified"))
      (node (ref "CN2") (pin "27") (pinfunction "27_27") (pintype "unspecified"))
      (node (ref "H1") (pin "2") (pinfunction "2_2") (pintype "unspecified"))
      (node (ref "R6") (pin "2") (pinfunction "2_2") (pintype "unspecified"))
      (node (ref "R7") (pin "2") (pinfunction "2_2") (pintype "unspecified"))
      (node (ref "R8") (pin "1") (pinfunction "1_1") (pintype "unspecified"))
      (node (ref "R9") (pin "1") (pinfunction "1_1") (pintype "unspecified"))
      (node (ref "SW1") (pin "1") (pinfunction "1_1") (pintype "unspecified"))
      (node (ref "U1") (pin "62") (pinfunction "VREG_PGND_62") (pintype "unspecified"))
      (node (ref "U1") (pin "81") (pinfunction "GND_81") (pintype "unspecified"))
      (node (ref "U2") (pin "4") (pinfunction "GND_4") (pintype "unspecified"))
      (node (ref "U3") (pin "2") (pinfunction "GND_2") (pintype "input"))
      (node (ref "U3") (pin "4") (pinfunction "GND_4") (pintype "input"))
      (node (ref "U4") (pin "2") (pinfunction "GND_2") (pintype "unspecified"))
      (node (ref "USB1") (pin "1") (pinfunction "SHELL_1") (pintype "unspecified"))
      (node (ref "USB1") (pin "2") (pinfunction "SHELL_2") (pintype "unspecified"))
      (node (ref "USB1") (pin "3") (pinfunction "SHELL_3") (pintype "unspecified"))
      (node (ref "USB1") (pin "4") (pinfunction "SHELL_4") (pintype "unspecified"))
      (node (ref "USB1") (pin "A1B12") (pinfunction "GND_A1B12") (pintype "unspecified"))
      (node (ref "USB1") (pin "B1A12") (pinfunction "GND_B1A12") (pintype "unspecified"))
    )
    (net (code "70") (name "Net-(C18-Pad2)") (class "Default")
      (node (ref "C18") (pin "2") (pinfunction "2_2") (pintype "unspecified"))
      (node (ref "R4") (pin "2") (pinfunction "2_2") (pintype "input"))
      (node (ref "U3") (pin "3") (pinfunction "3_3") (pintype "input"))
    )
    (net (code "71") (name "Net-(LED1-K)") (class "Default")
      (node (ref "LED1") (pin "1") (pinfunction "K_1") (pintype "unspecified"))
      (node (ref "R8") (pin "2") (pinfunction "2_2") (pintype "unspecified"))
    )
    (net (code "72") (name "Net-(LED2-K)") (class "Default")
      (node (ref "LED2") (pin "1") (pinfunction "K_1") (pintype "unspecified"))
      (node (ref "R9") (pin "2") (pinfunction "2_2") (pintype "unspecified"))
    )
    (net (code "73") (name "Net-(R5-Pad1)") (class "Default")
      (node (ref "R5") (pin "1") (pinfunction "1_1") (pintype "unspecified"))
      (node (ref "SW1") (pin "2") (pinfunction "2_2") (pintype "unspecified"))
    )
    (net (code "74") (name "Net-(USB1-CC1)") (class "Default")
      (node (ref "R7") (pin "1") (pinfunction "1_1") (pintype "unspecified"))
      (node (ref "USB1") (pin "A5") (pinfunction "CC1_A5") (pintype "unspecified"))
    )
    (net (code "75") (name "Net-(USB1-CC2)") (class "Default")
      (node (ref "R6") (pin "1") (pinfunction "1_1") (pintype "unspecified"))
      (node (ref "USB1") (pin "B5") (pinfunction "CC2_B5") (pintype "unspecified"))
    )
    (net (code "76") (name "VSYS") (class "Default")
      (node (ref "C20") (pin "2") (pinfunction "2_2") (pintype "input"))
      (node (ref "CN2") (pin "2") (pinfunction "2_2") (pintype "unspecified"))
      (node (ref "D1") (pin "1") (pinfunction "K_1") (pintype "unspecified"))
      (node (ref "U4") (pin "1") (pinfunction "IN_1") (pintype "unspecified"))
      (node (ref "U4") (pin "3") (pinfunction "EN_3") (pintype "unspecified"))
    )
    (net (code "77") (name "unconnected-(U2-EP-Pad9)") (class "Default")
      (node (ref "U2") (pin "9") (pinfunction "EP_9") (pintype "unspecified+no_connect"))
    )
    (net (code "78") (name "unconnected-(U4-NC-Pad4)") (class "Default")
      (node (ref "U4") (pin "4") (pinfunction "NC_4") (pintype "unspecified+no_connect"))
    )
    (net (code "79") (name "unconnected-(USB1-SBU1-PadA8)") (class "Default")
      (node (ref "USB1") (pin "A8") (pinfunction "SBU1_A8") (pintype "unspecified+no_connect"))
    )
    (net (code "80") (name "unconnected-(USB1-SBU2-PadB8)") (class "Default")
      (node (ref "USB1") (pin "B8") (pinfunction "SBU2_B8") (pintype "unspecified+no_connect"))
    )
  )
)
